# 7_5in_display.net
KiCad netlist of a schematic drawn in EAGLE
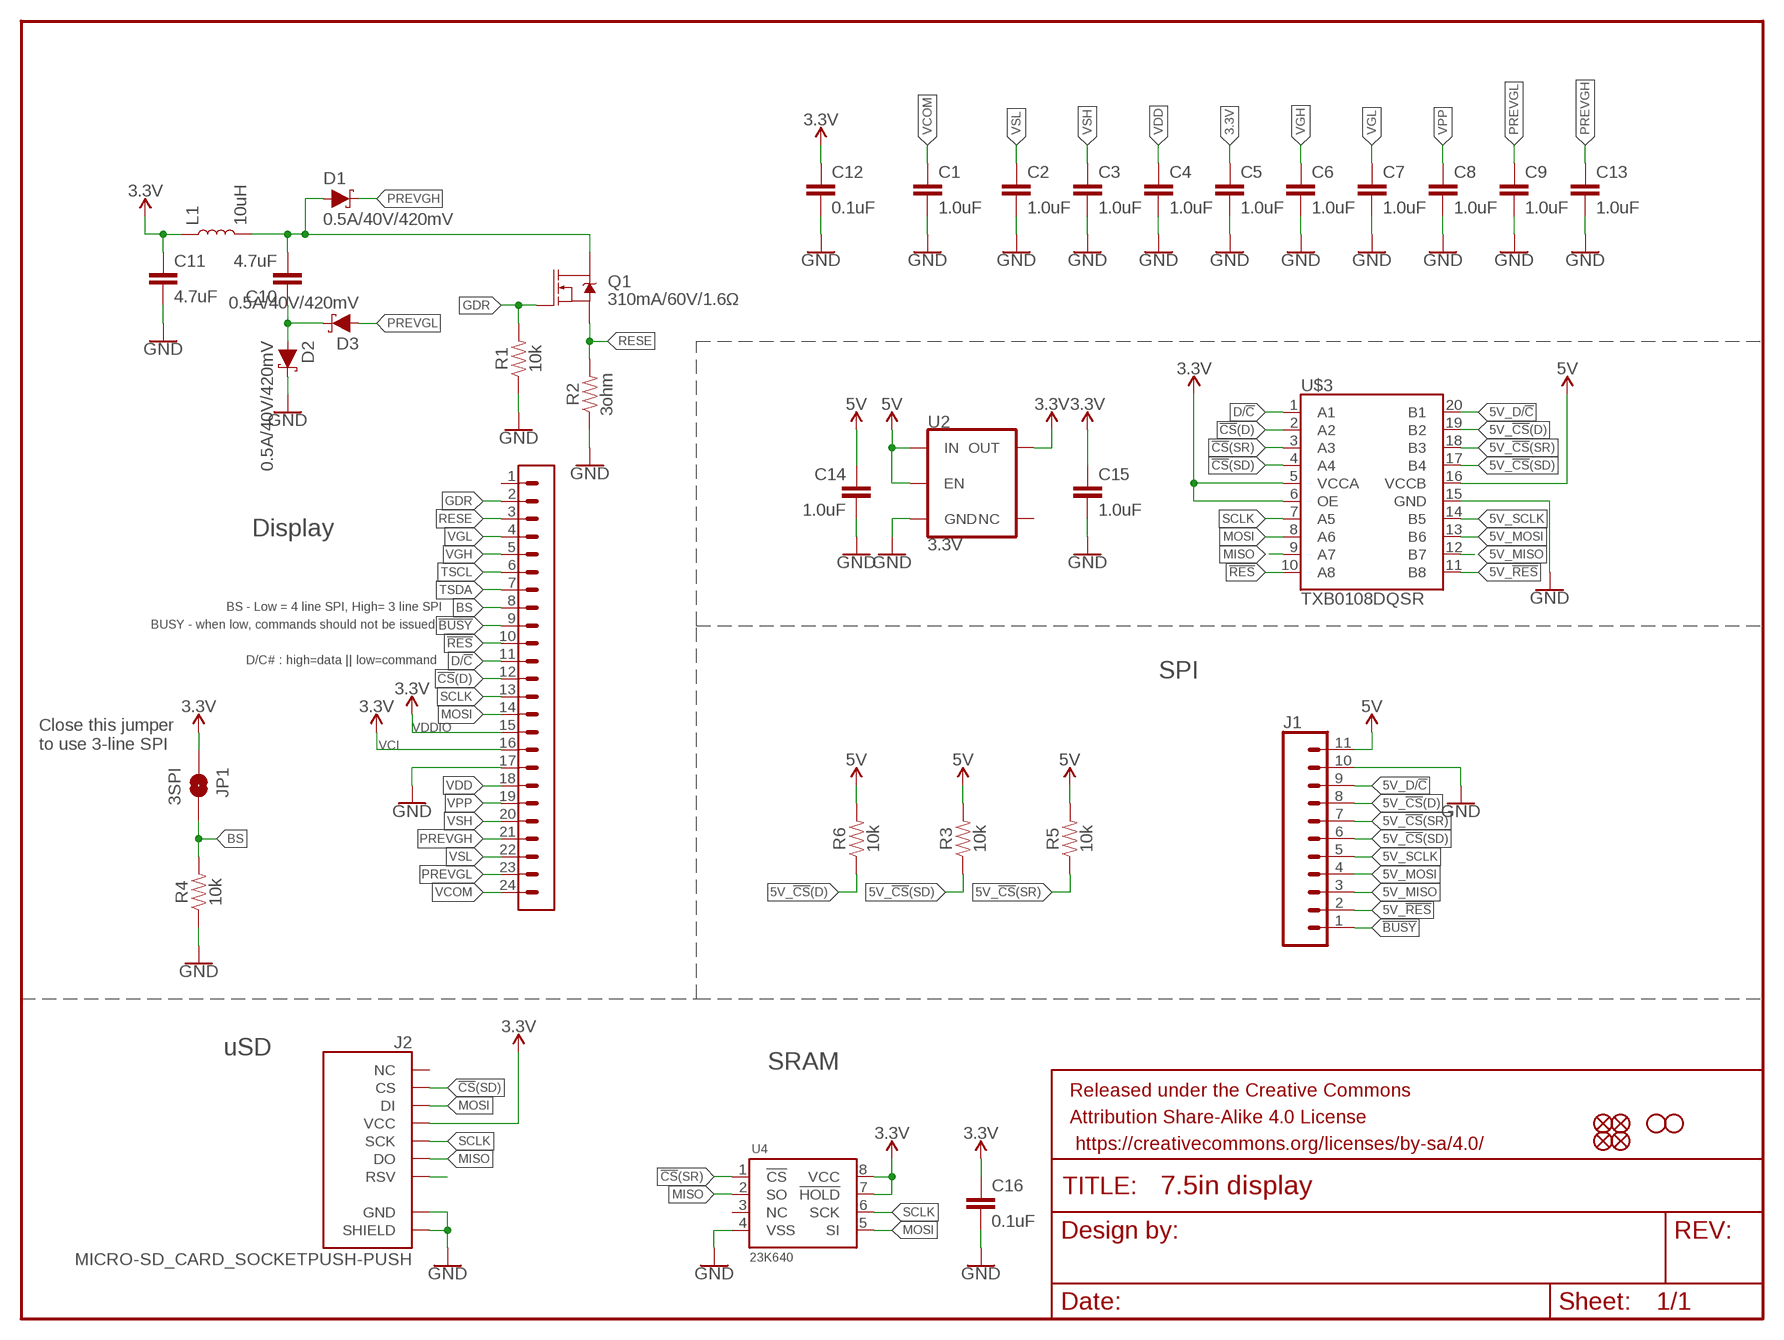
[diagram p0: schematic, sheet 1]

(export (version "E")
  (design (tool "Eeschema 10.0.6"))
  (components
    (comp (ref "C1")
      (value "1.0uF")
      (footprint "eagle-import:0603")
      (libsource (lib "eagle-import") (part "1.0UF-0603-16V-10%"))
    )
    (comp (ref "C2")
      (value "1.0uF")
      (footprint "eagle-import:0805")
      (libsource (lib "eagle-import") (part "1.0UF-0805-25V-10%"))
    )
    (comp (ref "C3")
      (value "1.0uF")
      (footprint "eagle-import:0805")
      (libsource (lib "eagle-import") (part "1.0UF-0805-25V-10%"))
    )
    (comp (ref "C4")
      (value "1.0uF")
      (footprint "eagle-import:0805")
      (libsource (lib "eagle-import") (part "1.0UF-0805-25V-10%"))
    )
    (comp (ref "C5")
      (value "1.0uF")
      (footprint "eagle-import:0805")
      (libsource (lib "eagle-import") (part "1.0UF-0805-25V-10%"))
    )
    (comp (ref "C6")
      (value "1.0uF")
      (footprint "eagle-import:0805")
      (libsource (lib "eagle-import") (part "1.0UF-0805-25V-10%"))
    )
    (comp (ref "C7")
      (value "1.0uF")
      (footprint "eagle-import:0805")
      (libsource (lib "eagle-import") (part "1.0UF-0805-25V-10%"))
    )
    (comp (ref "C8")
      (value "1.0uF")
      (footprint "eagle-import:0805")
      (libsource (lib "eagle-import") (part "1.0UF-0805-25V-10%"))
    )
    (comp (ref "C9")
      (value "1.0uF")
      (footprint "eagle-import:0805")
      (libsource (lib "eagle-import") (part "1.0UF-0805-25V-10%"))
    )
    (comp (ref "C10")
      (value "4.7uF")
      (footprint "eagle-import:0805")
      (libsource (lib "eagle-import") (part "22UF-0805-6.3V-20%"))
    )
    (comp (ref "C11")
      (value "4.7uF")
      (footprint "eagle-import:0805")
      (libsource (lib "eagle-import") (part "22UF-0805-6.3V-20%"))
    )
    (comp (ref "C12")
      (value "0.1uF")
      (footprint "eagle-import:0603")
      (libsource (lib "eagle-import") (part "0.1UF-0603-25V-(+80/-20%)"))
    )
    (comp (ref "C13")
      (value "1.0uF")
      (footprint "eagle-import:0805")
      (libsource (lib "eagle-import") (part "1.0UF-0805-25V-10%"))
    )
    (comp (ref "C14")
      (value "1.0uF")
      (footprint "eagle-import:0603")
      (libsource (lib "eagle-import") (part "1.0UF-0603-16V-10%"))
    )
    (comp (ref "C15")
      (value "1.0uF")
      (footprint "eagle-import:0603")
      (libsource (lib "eagle-import") (part "1.0UF-0603-16V-10%"))
    )
    (comp (ref "C16")
      (value "0.1uF")
      (footprint "eagle-import:0603")
      (libsource (lib "eagle-import") (part "0.1UF-0603-25V-(+80/-20%)"))
    )
    (comp (ref "D1")
      (value "0.5A/40V/420mV")
      (footprint "eagle-import:SOD-323")
      (libsource (lib "eagle-import") (part "DIODE-SCHOTTKY-PMEG4005EJ"))
    )
    (comp (ref "D2")
      (value "0.5A/40V/420mV")
      (footprint "eagle-import:SOD-323")
      (libsource (lib "eagle-import") (part "DIODE-SCHOTTKY-PMEG4005EJ"))
    )
    (comp (ref "D3")
      (value "0.5A/40V/420mV")
      (footprint "eagle-import:SOD-323")
      (libsource (lib "eagle-import") (part "DIODE-SCHOTTKY-PMEG4005EJ"))
    )
    (comp (ref "FD1")
      (value "FIDUCIALUFIDUCIAL")
      (footprint "eagle-import:FIDUCIAL-MICRO")
      (libsource (lib "eagle-import") (part "FIDUCIALUFIDUCIAL"))
    )
    (comp (ref "FD2")
      (value "FIDUCIALUFIDUCIAL")
      (footprint "eagle-import:FIDUCIAL-MICRO")
      (libsource (lib "eagle-import") (part "FIDUCIALUFIDUCIAL"))
    )
    (comp (ref "FD3")
      (value "FIDUCIALUFIDUCIAL")
      (footprint "eagle-import:FIDUCIAL-MICRO")
      (libsource (lib "eagle-import") (part "FIDUCIALUFIDUCIAL"))
    )
    (comp (ref "FD4")
      (value "FIDUCIALUFIDUCIAL")
      (footprint "eagle-import:FIDUCIAL-MICRO")
      (libsource (lib "eagle-import") (part "FIDUCIALUFIDUCIAL"))
    )
    (comp (ref "FRAME1")
      (value "FRAME-LETTER")
      (footprint "eagle-import:CREATIVE_COMMONS")
      (libsource (lib "eagle-import") (part "FRAME-LETTER"))
    )
    (comp (ref "H1")
      (value "STAND-OFF")
      (footprint "eagle-import:STAND-OFF")
      (libsource (lib "eagle-import") (part "STAND-OFF"))
    )
    (comp (ref "H2")
      (value "STAND-OFF")
      (footprint "eagle-import:STAND-OFF")
      (libsource (lib "eagle-import") (part "STAND-OFF"))
    )
    (comp (ref "J1")
      (value "CONN_111X11_NO_SILK")
      (footprint "eagle-import:1X11_NO_SILK")
      (libsource (lib "eagle-import") (part "CONN_111X11_NO_SILK"))
    )
    (comp (ref "J2")
      (value "MICRO-SD_CARD_SOCKETPUSH-PUSH")
      (footprint "eagle-import:MICRO-SD-SOCKET")
      (libsource (lib "eagle-import") (part "MICRO-SD_CARD_SOCKETPUSH-PUSH"))
    )
    (comp (ref "JP1")
      (value "3SPI")
      (footprint "eagle-import:SMT-JUMPER_2_NO_SILK")
      (libsource (lib "eagle-import") (part "JUMPER-SMT_2_NO_SILK"))
    )
    (comp (ref "L1")
      (value "10uH")
      (footprint "eagle-import:INDUCTOR_4.7UH")
      (libsource (lib "eagle-import") (part "INDUCTOR-CDRH-10UH"))
    )
    (comp (ref "Q1")
      (value "310mA/60V/1.6Ω")
      (footprint "eagle-import:SOT323")
      (libsource (lib "eagle-import") (part "MOSFET-NCH-2N7002PW"))
    )
    (comp (ref "R1")
      (value "10k")
      (footprint "eagle-import:0603")
      (libsource (lib "eagle-import") (part "10KOHM-0603-1/10W-1%"))
    )
    (comp (ref "R2")
      (value "3ohm")
      (footprint "eagle-import:0603")
      (libsource (lib "eagle-import") (part "RESISTOR0603"))
    )
    (comp (ref "R3")
      (value "10k")
      (footprint "eagle-import:0603")
      (libsource (lib "eagle-import") (part "10KOHM-0603-1/10W-1%"))
    )
    (comp (ref "R4")
      (value "10k")
      (footprint "eagle-import:0603")
      (libsource (lib "eagle-import") (part "10KOHM-0603-1/10W-1%"))
    )
    (comp (ref "R5")
      (value "10k")
      (footprint "eagle-import:0603")
      (libsource (lib "eagle-import") (part "10KOHM-0603-1/10W-1%"))
    )
    (comp (ref "R6")
      (value "10k")
      (footprint "eagle-import:0603")
      (libsource (lib "eagle-import") (part "10KOHM-0603-1/10W-1%"))
    )
    (comp (ref "U$1")
      (value "24_PIN_FPC_0.5MM")
      (footprint "eagle-import:24_PIN_FPC_0.5MM")
      (libsource (lib "eagle-import") (part "24_PIN_FPC_0.5MM"))
    )
    (comp (ref "U$3")
      (value "TXB0108DQSR")
      (footprint "eagle-import:UFDFN-20")
      (libsource (lib "eagle-import") (part "TXB0108"))
    )
    (comp (ref "U2")
      (value "3.3V")
      (footprint "eagle-import:SOT23-5")
      (libsource (lib "eagle-import") (part "V_REG_AP2112K-3.3V"))
    )
    (comp (ref "U4")
      (value "23K640")
      (footprint "eagle-import:SO08")
      (libsource (lib "eagle-import") (part "23K640"))
    )
  )
  (nets
    (net (code "1") (name "/5V_D{slash}~{C}") (class "Default")
      (node (ref "J1") (pin "9") (pinfunction "9_9") (pintype "passive"))
      (node (ref "U$3") (pin "20") (pinfunction "B1_20") (pintype "bidirectional"))
    )
    (net (code "2") (name "/5V_~{CS}(D)") (class "Default")
      (node (ref "J1") (pin "8") (pinfunction "8_8") (pintype "passive"))
      (node (ref "R6") (pin "1") (pinfunction "1_1") (pintype "passive"))
      (node (ref "U$3") (pin "19") (pinfunction "B2_19") (pintype "bidirectional"))
    )
    (net (code "3") (name "/5V_~{CS}(SD)") (class "Default")
      (node (ref "J1") (pin "6") (pinfunction "6_6") (pintype "passive"))
      (node (ref "R3") (pin "1") (pinfunction "1_1") (pintype "passive"))
      (node (ref "U$3") (pin "17") (pinfunction "B4_17") (pintype "bidirectional"))
    )
    (net (code "4") (name "/5V_~{CS}(SR)") (class "Default")
      (node (ref "J1") (pin "7") (pinfunction "7_7") (pintype "passive"))
      (node (ref "R5") (pin "1") (pinfunction "1_1") (pintype "passive"))
      (node (ref "U$3") (pin "18") (pinfunction "B3_18") (pintype "bidirectional"))
    )
    (net (code "5") (name "/5V_~{RES}") (class "Default")
      (node (ref "J1") (pin "2") (pinfunction "2_2") (pintype "passive"))
      (node (ref "U$3") (pin "11") (pinfunction "B8_11") (pintype "bidirectional"))
    )
    (net (code "6") (name "/D{slash}~{C}") (class "Default")
      (node (ref "U$1") (pin "11") (pinfunction "11_11") (pintype "bidirectional"))
      (node (ref "U$3") (pin "1") (pinfunction "A1_1") (pintype "bidirectional"))
    )
    (net (code "7") (name "/~{BUSY}") (class "Default")
      (node (ref "J1") (pin "1") (pinfunction "1_1") (pintype "passive"))
      (node (ref "U$1") (pin "9") (pinfunction "9_9") (pintype "bidirectional"))
    )
    (net (code "8") (name "/~{CS}(D)") (class "Default")
      (node (ref "U$1") (pin "12") (pinfunction "12_12") (pintype "bidirectional"))
      (node (ref "U$3") (pin "2") (pinfunction "A2_2") (pintype "bidirectional"))
    )
    (net (code "9") (name "/~{CS}(SD)") (class "Default")
      (node (ref "J2") (pin "CS") (pinfunction "CS_CS") (pintype "bidirectional"))
      (node (ref "U$3") (pin "4") (pinfunction "A4_4") (pintype "bidirectional"))
    )
    (net (code "10") (name "/~{CS}(SR)") (class "Default")
      (node (ref "U$3") (pin "3") (pinfunction "A3_3") (pintype "bidirectional"))
      (node (ref "U4") (pin "1") (pinfunction "~{CS}_1") (pintype "bidirectional"))
    )
    (net (code "11") (name "/~{RES}") (class "Default")
      (node (ref "U$1") (pin "10") (pinfunction "10_10") (pintype "bidirectional"))
      (node (ref "U$3") (pin "10") (pinfunction "A8_10") (pintype "bidirectional"))
    )
    (net (code "12") (name "3.3V") (class "Default")
      (node (ref "C11") (pin "1") (pinfunction "1_1") (pintype "passive"))
      (node (ref "C12") (pin "1") (pinfunction "1_1") (pintype "passive"))
      (node (ref "C15") (pin "1") (pinfunction "1_1") (pintype "passive"))
      (node (ref "C16") (pin "1") (pinfunction "1_1") (pintype "passive"))
      (node (ref "C5") (pin "1") (pinfunction "1_1") (pintype "passive"))
      (node (ref "J2") (pin "VCC") (pinfunction "VCC_VCC") (pintype "bidirectional"))
      (node (ref "JP1") (pin "1") (pinfunction "1_1") (pintype "passive"))
      (node (ref "L1") (pin "P$1") (pinfunction "1_P$1") (pintype "passive"))
      (node (ref "U$1") (pin "15") (pinfunction "15_15") (pintype "bidirectional"))
      (node (ref "U$1") (pin "16") (pinfunction "16_16") (pintype "bidirectional"))
      (node (ref "U$3") (pin "5") (pinfunction "VCCA_5") (pintype "bidirectional"))
      (node (ref "U$3") (pin "6") (pinfunction "OE_6") (pintype "bidirectional"))
      (node (ref "U2") (pin "5") (pinfunction "OUT_5") (pintype "passive"))
      (node (ref "U4") (pin "7") (pinfunction "~{HOLD}_7") (pintype "bidirectional"))
      (node (ref "U4") (pin "8") (pinfunction "VCC_8") (pintype "bidirectional"))
    )
    (net (code "13") (name "5V") (class "Default")
      (node (ref "C14") (pin "1") (pinfunction "1_1") (pintype "passive"))
      (node (ref "J1") (pin "11") (pinfunction "11_11") (pintype "passive"))
      (node (ref "R3") (pin "2") (pinfunction "2_2") (pintype "passive"))
      (node (ref "R5") (pin "2") (pinfunction "2_2") (pintype "passive"))
      (node (ref "R6") (pin "2") (pinfunction "2_2") (pintype "passive"))
      (node (ref "U$3") (pin "16") (pinfunction "VCCB_16") (pintype "bidirectional"))
      (node (ref "U2") (pin "1") (pinfunction "IN_1") (pintype "input"))
      (node (ref "U2") (pin "3") (pinfunction "EN_3") (pintype "input"))
    )
    (net (code "14") (name "5V_MISO") (class "Default")
      (node (ref "J1") (pin "3") (pinfunction "3_3") (pintype "passive"))
      (node (ref "U$3") (pin "12") (pinfunction "B7_12") (pintype "bidirectional"))
    )
    (net (code "15") (name "5V_MOSI") (class "Default")
      (node (ref "J1") (pin "4") (pinfunction "4_4") (pintype "passive"))
      (node (ref "U$3") (pin "13") (pinfunction "B6_13") (pintype "bidirectional"))
    )
    (net (code "16") (name "5V_SCLK") (class "Default")
      (node (ref "J1") (pin "5") (pinfunction "5_5") (pintype "passive"))
      (node (ref "U$3") (pin "14") (pinfunction "B5_14") (pintype "bidirectional"))
    )
    (net (code "17") (name "BS") (class "Default")
      (node (ref "JP1") (pin "2") (pinfunction "2_2") (pintype "passive"))
      (node (ref "R4") (pin "2") (pinfunction "2_2") (pintype "passive"))
      (node (ref "U$1") (pin "8") (pinfunction "8_8") (pintype "bidirectional"))
    )
    (net (code "18") (name "GDR") (class "Default")
      (node (ref "Q1") (pin "1") (pinfunction "G_1") (pintype "bidirectional"))
      (node (ref "R1") (pin "2") (pinfunction "2_2") (pintype "passive"))
      (node (ref "U$1") (pin "2") (pinfunction "2_2") (pintype "bidirectional"))
    )
    (net (code "19") (name "GND") (class "Default")
      (node (ref "C1") (pin "2") (pinfunction "2_2") (pintype "passive"))
      (node (ref "C11") (pin "2") (pinfunction "2_2") (pintype "passive"))
      (node (ref "C12") (pin "2") (pinfunction "2_2") (pintype "passive"))
      (node (ref "C13") (pin "2") (pinfunction "2_2") (pintype "passive"))
      (node (ref "C14") (pin "2") (pinfunction "2_2") (pintype "passive"))
      (node (ref "C15") (pin "2") (pinfunction "2_2") (pintype "passive"))
      (node (ref "C16") (pin "2") (pinfunction "2_2") (pintype "passive"))
      (node (ref "C2") (pin "2") (pinfunction "2_2") (pintype "passive"))
      (node (ref "C3") (pin "2") (pinfunction "2_2") (pintype "passive"))
      (node (ref "C4") (pin "2") (pinfunction "2_2") (pintype "passive"))
      (node (ref "C5") (pin "2") (pinfunction "2_2") (pintype "passive"))
      (node (ref "C6") (pin "2") (pinfunction "2_2") (pintype "passive"))
      (node (ref "C7") (pin "2") (pinfunction "2_2") (pintype "passive"))
      (node (ref "C8") (pin "2") (pinfunction "2_2") (pintype "passive"))
      (node (ref "C9") (pin "2") (pinfunction "2_2") (pintype "passive"))
      (node (ref "D2") (pin "C") (pinfunction "C_C") (pintype "passive"))
      (node (ref "J1") (pin "10") (pinfunction "10_10") (pintype "passive"))
      (node (ref "J2") (pin "CD1") (pinfunction "SHIELD_CD1") (pintype "bidirectional"))
      (node (ref "J2") (pin "GND") (pinfunction "GND_GND") (pintype "bidirectional"))
      (node (ref "R1") (pin "1") (pinfunction "1_1") (pintype "passive"))
      (node (ref "R2") (pin "1") (pinfunction "1_1") (pintype "passive"))
      (node (ref "R4") (pin "1") (pinfunction "1_1") (pintype "passive"))
      (node (ref "U$1") (pin "17") (pinfunction "17_17") (pintype "bidirectional"))
      (node (ref "U$3") (pin "15") (pinfunction "GND_15") (pintype "bidirectional"))
      (node (ref "U2") (pin "2") (pinfunction "GND_2") (pintype "input"))
      (node (ref "U4") (pin "4") (pinfunction "VSS_4") (pintype "bidirectional"))
    )
    (net (code "20") (name "MISO") (class "Default")
      (node (ref "J2") (pin "DO") (pinfunction "DO_DO") (pintype "bidirectional"))
      (node (ref "U$3") (pin "9") (pinfunction "A7_9") (pintype "bidirectional"))
      (node (ref "U4") (pin "2") (pinfunction "SO_2") (pintype "bidirectional"))
    )
    (net (code "21") (name "MOSI") (class "Default")
      (node (ref "J2") (pin "DI") (pinfunction "DI_DI") (pintype "bidirectional"))
      (node (ref "U$1") (pin "14") (pinfunction "14_14") (pintype "bidirectional"))
      (node (ref "U$3") (pin "8") (pinfunction "A6_8") (pintype "bidirectional"))
      (node (ref "U4") (pin "5") (pinfunction "SI_5") (pintype "bidirectional"))
    )
    (net (code "22") (name "Net-(C10-Pad1)") (class "Default")
      (node (ref "C10") (pin "1") (pinfunction "1_1") (pintype "passive"))
      (node (ref "D2") (pin "A") (pinfunction "A_A") (pintype "passive"))
      (node (ref "D3") (pin "C") (pinfunction "C_C") (pintype "passive"))
    )
    (net (code "23") (name "Net-(L1-2)") (class "Default")
      (node (ref "C10") (pin "2") (pinfunction "2_2") (pintype "passive"))
      (node (ref "D1") (pin "A") (pinfunction "A_A") (pintype "passive"))
      (node (ref "L1") (pin "P$2") (pinfunction "2_P$2") (pintype "passive"))
      (node (ref "Q1") (pin "3") (pinfunction "D_3") (pintype "bidirectional"))
    )
    (net (code "24") (name "PREVGH") (class "Default")
      (node (ref "C13") (pin "1") (pinfunction "1_1") (pintype "passive"))
      (node (ref "D1") (pin "C") (pinfunction "C_C") (pintype "passive"))
      (node (ref "U$1") (pin "21") (pinfunction "21_21") (pintype "bidirectional"))
    )
    (net (code "25") (name "PREVGL") (class "Default")
      (node (ref "C9") (pin "1") (pinfunction "1_1") (pintype "passive"))
      (node (ref "D3") (pin "A") (pinfunction "A_A") (pintype "passive"))
      (node (ref "U$1") (pin "23") (pinfunction "23_23") (pintype "bidirectional"))
    )
    (net (code "26") (name "RESE") (class "Default")
      (node (ref "Q1") (pin "2") (pinfunction "S_2") (pintype "bidirectional"))
      (node (ref "R2") (pin "2") (pinfunction "2_2") (pintype "passive"))
      (node (ref "U$1") (pin "3") (pinfunction "3_3") (pintype "bidirectional"))
    )
    (net (code "27") (name "SCLK") (class "Default")
      (node (ref "J2") (pin "SCLK") (pinfunction "SCK_SCLK") (pintype "bidirectional"))
      (node (ref "U$1") (pin "13") (pinfunction "13_13") (pintype "bidirectional"))
      (node (ref "U$3") (pin "7") (pinfunction "A5_7") (pintype "bidirectional"))
      (node (ref "U4") (pin "6") (pinfunction "SCK_6") (pintype "bidirectional"))
    )
    (net (code "28") (name "TSCL") (class "Default")
      (node (ref "U$1") (pin "6") (pinfunction "6_6") (pintype "bidirectional"))
    )
    (net (code "29") (name "TSDA") (class "Default")
      (node (ref "U$1") (pin "7") (pinfunction "7_7") (pintype "bidirectional"))
    )
    (net (code "30") (name "VCOM") (class "Default")
      (node (ref "C1") (pin "1") (pinfunction "1_1") (pintype "passive"))
      (node (ref "U$1") (pin "24") (pinfunction "24_24") (pintype "bidirectional"))
    )
    (net (code "31") (name "VDD") (class "Default")
      (node (ref "C4") (pin "1") (pinfunction "1_1") (pintype "passive"))
      (node (ref "U$1") (pin "18") (pinfunction "18_18") (pintype "bidirectional"))
    )
    (net (code "32") (name "VGH") (class "Default")
      (node (ref "C6") (pin "1") (pinfunction "1_1") (pintype "passive"))
      (node (ref "U$1") (pin "5") (pinfunction "5_5") (pintype "bidirectional"))
    )
    (net (code "33") (name "VGL") (class "Default")
      (node (ref "C7") (pin "1") (pinfunction "1_1") (pintype "passive"))
      (node (ref "U$1") (pin "4") (pinfunction "4_4") (pintype "bidirectional"))
    )
    (net (code "34") (name "VPP") (class "Default")
      (node (ref "C8") (pin "1") (pinfunction "1_1") (pintype "passive"))
      (node (ref "U$1") (pin "19") (pinfunction "19_19") (pintype "bidirectional"))
    )
    (net (code "35") (name "VSH") (class "Default")
      (node (ref "C3") (pin "1") (pinfunction "1_1") (pintype "passive"))
      (node (ref "U$1") (pin "20") (pinfunction "20_20") (pintype "bidirectional"))
    )
    (net (code "36") (name "VSL") (class "Default")
      (node (ref "C2") (pin "1") (pinfunction "1_1") (pintype "passive"))
      (node (ref "U$1") (pin "22") (pinfunction "22_22") (pintype "bidirectional"))
    )
    (net (code "37") (name "unconnected-(J2-NC-PadRSV2)") (class "Default")
      (node (ref "J2") (pin "RSV2") (pinfunction "NC_RSV2") (pintype "bidirectional"))
    )
    (net (code "38") (name "unconnected-(J2-RSV-PadRSV1)") (class "Default")
      (node (ref "J2") (pin "RSV1") (pinfunction "RSV_RSV1") (pintype "bidirectional"))
    )
    (net (code "39") (name "unconnected-(U$1-Pad1)") (class "Default")
      (node (ref "U$1") (pin "1") (pinfunction "1_1") (pintype "bidirectional"))
    )
    (net (code "40") (name "unconnected-(U2-NC-Pad4)") (class "Default")
      (node (ref "U2") (pin "4") (pinfunction "NC_4") (pintype "no_connect"))
    )
    (net (code "41") (name "unconnected-(U4-NC-Pad3)") (class "Default")
      (node (ref "U4") (pin "3") (pinfunction "NC_3") (pintype "bidirectional"))
    )
  )
)
